# Dosing_CTRLR_HMI.net
KiCad netlist of a schematic drawn in EAGLE
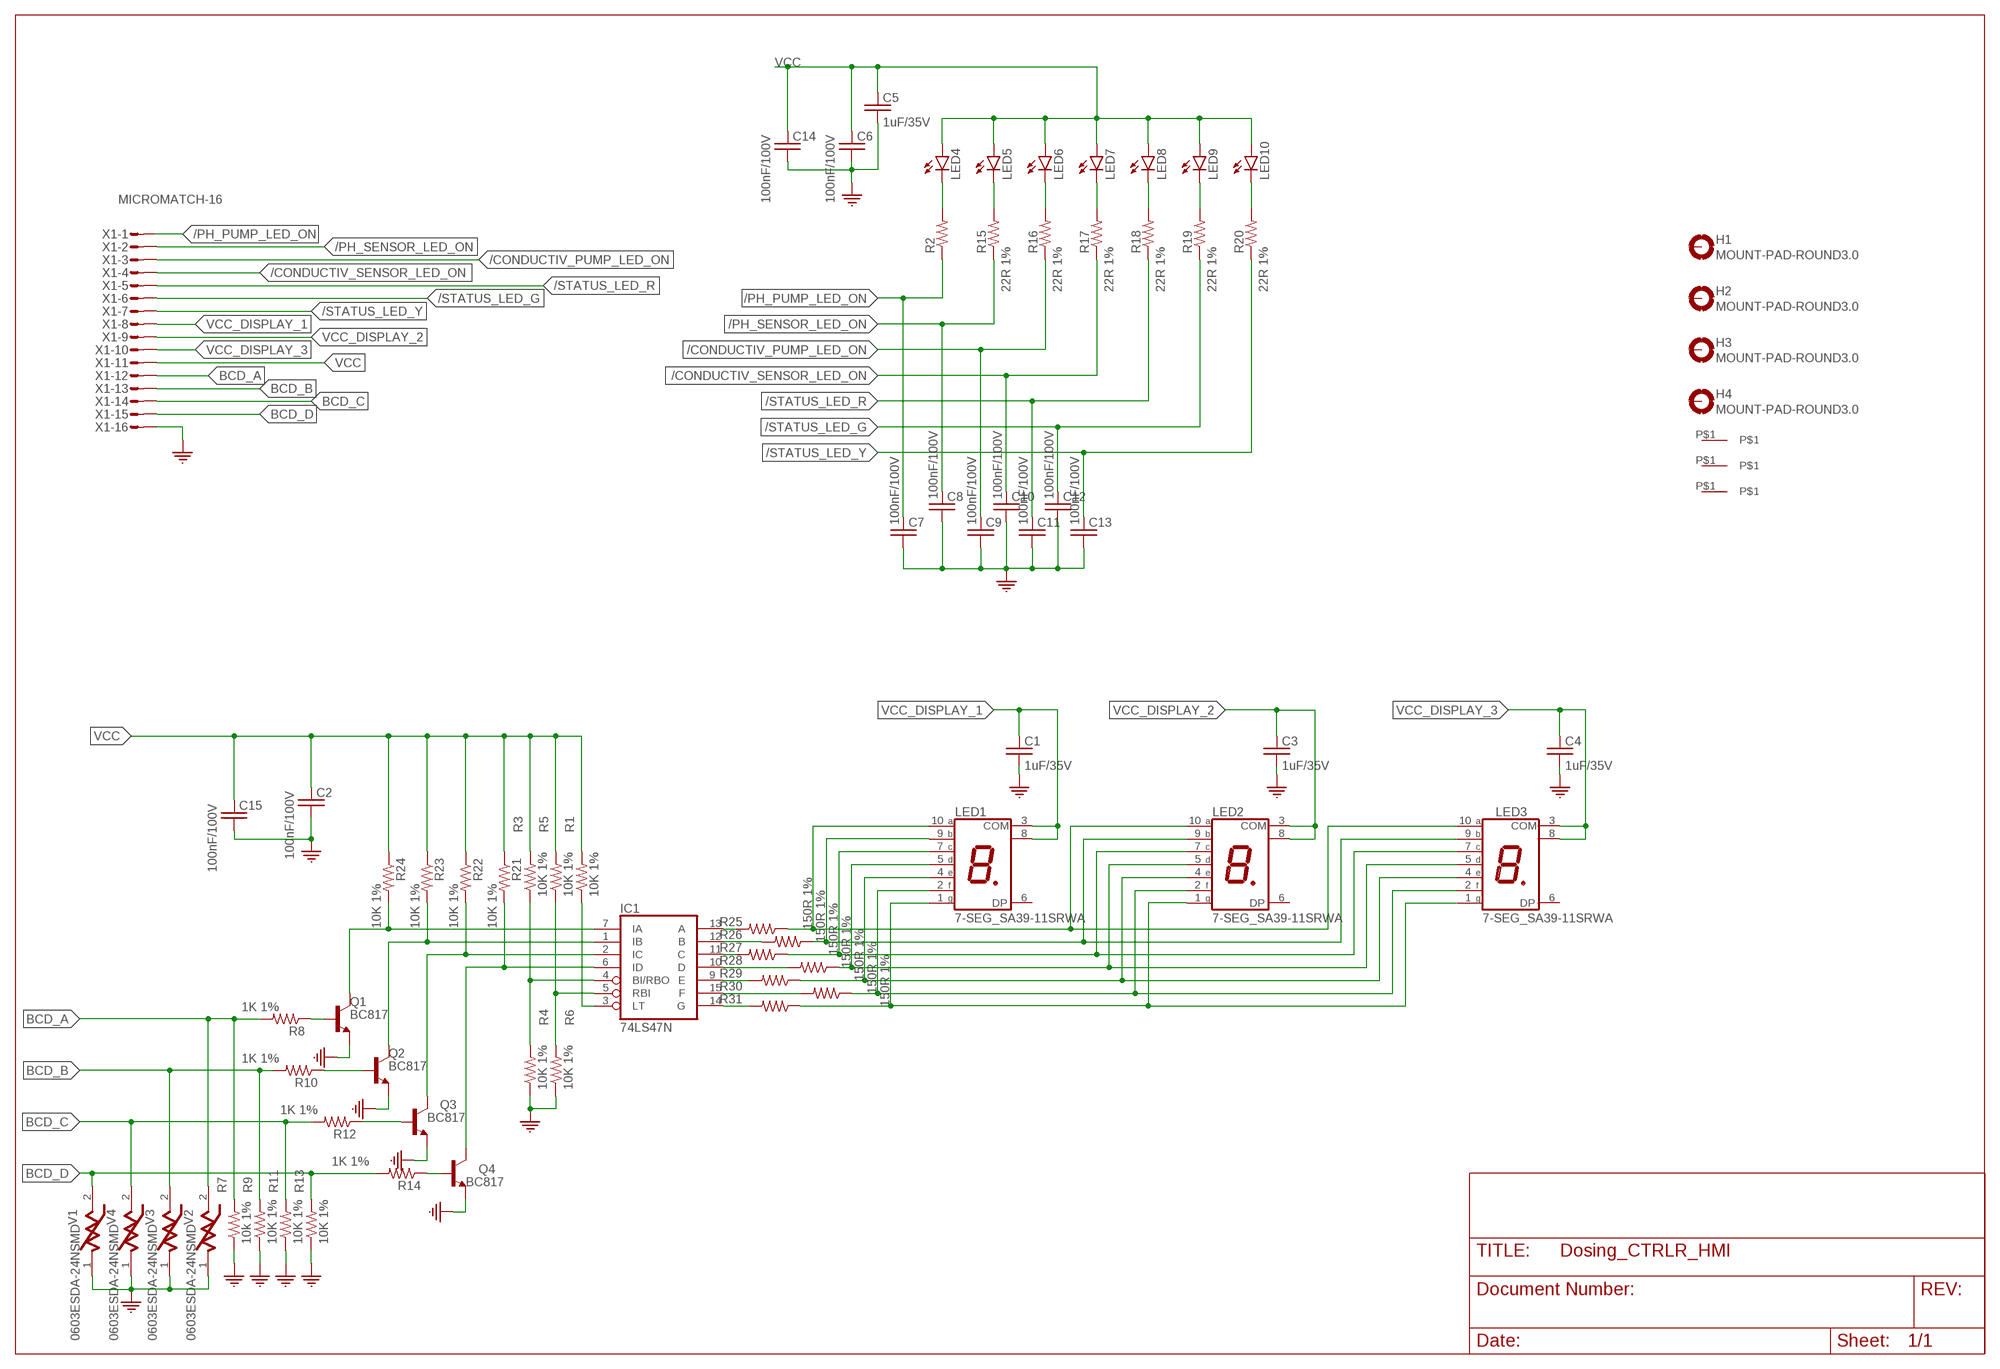
[diagram p0: schematic, sheet 1]

(export (version "E")
  (design (tool "Eeschema 10.0.6"))
  (components
    (comp (ref "C1")
      (value "1uF/35V")
      (footprint "eagle-import:EIA0603")
      (libsource (lib "eagle-import") (part "C_0603EIA0603"))
    )
    (comp (ref "C2")
      (value "100nF/100V")
      (footprint "eagle-import:EIA0603")
      (libsource (lib "eagle-import") (part "C_0603EIA0603"))
    )
    (comp (ref "C3")
      (value "1uF/35V")
      (footprint "eagle-import:EIA0603")
      (libsource (lib "eagle-import") (part "C_0603EIA0603"))
    )
    (comp (ref "C4")
      (value "1uF/35V")
      (footprint "eagle-import:EIA0603")
      (libsource (lib "eagle-import") (part "C_0603EIA0603"))
    )
    (comp (ref "C5")
      (value "1uF/35V")
      (footprint "eagle-import:EIA0603")
      (libsource (lib "eagle-import") (part "C_0603EIA0603"))
    )
    (comp (ref "C6")
      (value "100nF/100V")
      (footprint "eagle-import:EIA0603")
      (libsource (lib "eagle-import") (part "C_0603EIA0603"))
    )
    (comp (ref "C7")
      (value "100nF/100V")
      (footprint "eagle-import:EIA0603")
      (libsource (lib "eagle-import") (part "C_0603EIA0603"))
    )
    (comp (ref "C8")
      (value "100nF/100V")
      (footprint "eagle-import:EIA0603")
      (libsource (lib "eagle-import") (part "C_0603EIA0603"))
    )
    (comp (ref "C9")
      (value "100nF/100V")
      (footprint "eagle-import:EIA0603")
      (libsource (lib "eagle-import") (part "C_0603EIA0603"))
    )
    (comp (ref "C10")
      (value "100nF/100V")
      (footprint "eagle-import:EIA0603")
      (libsource (lib "eagle-import") (part "C_0603EIA0603"))
    )
    (comp (ref "C11")
      (value "100nF/100V")
      (footprint "eagle-import:EIA0603")
      (libsource (lib "eagle-import") (part "C_0603EIA0603"))
    )
    (comp (ref "C12")
      (value "100nF/100V")
      (footprint "eagle-import:EIA0603")
      (libsource (lib "eagle-import") (part "C_0603EIA0603"))
    )
    (comp (ref "C13")
      (value "100nF/100V")
      (footprint "eagle-import:EIA0603")
      (libsource (lib "eagle-import") (part "C_0603EIA0603"))
    )
    (comp (ref "C14")
      (value "100nF/100V")
      (footprint "eagle-import:EIA0603")
      (libsource (lib "eagle-import") (part "C_0603EIA0603"))
    )
    (comp (ref "C15")
      (value "100nF/100V")
      (footprint "eagle-import:EIA0603")
      (libsource (lib "eagle-import") (part "C_0603EIA0603"))
    )
    (comp (ref "FID1")
      (value "FIDUCIAL")
      (footprint "eagle-import:FIDUCIAL")
      (libsource (lib "eagle-import") (part "FIDUCIAL"))
    )
    (comp (ref "FID2")
      (value "FIDUCIAL")
      (footprint "eagle-import:FIDUCIAL")
      (libsource (lib "eagle-import") (part "FIDUCIAL"))
    )
    (comp (ref "FID3")
      (value "FIDUCIAL")
      (footprint "eagle-import:FIDUCIAL")
      (libsource (lib "eagle-import") (part "FIDUCIAL"))
    )
    (comp (ref "H1")
      (value "MOUNT-PAD-ROUND3.0")
      (footprint "eagle-import:3,0-PAD")
      (libsource (lib "eagle-import") (part "MOUNT-PAD-ROUND3.0"))
    )
    (comp (ref "H2")
      (value "MOUNT-PAD-ROUND3.0")
      (footprint "eagle-import:3,0-PAD")
      (libsource (lib "eagle-import") (part "MOUNT-PAD-ROUND3.0"))
    )
    (comp (ref "H3")
      (value "MOUNT-PAD-ROUND3.0")
      (footprint "eagle-import:3,0-PAD")
      (libsource (lib "eagle-import") (part "MOUNT-PAD-ROUND3.0"))
    )
    (comp (ref "H4")
      (value "MOUNT-PAD-ROUND3.0")
      (footprint "eagle-import:3,0-PAD")
      (libsource (lib "eagle-import") (part "MOUNT-PAD-ROUND3.0"))
    )
    (comp (ref "IC1")
      (value "74LS47N")
      (footprint "eagle-import:DIL16")
      (libsource (lib "eagle-import") (part "7447NLS"))
    )
    (comp (ref "LED1")
      (value "7-SEG_SA39-11SRWA")
      (footprint "eagle-import:SA39-11SRWA")
      (libsource (lib "eagle-import") (part "7-SEG_SA39-11SRWA"))
    )
    (comp (ref "LED2")
      (value "7-SEG_SA39-11SRWA")
      (footprint "eagle-import:SA39-11SRWA")
      (libsource (lib "eagle-import") (part "7-SEG_SA39-11SRWA"))
    )
    (comp (ref "LED3")
      (value "7-SEG_SA39-11SRWA")
      (footprint "eagle-import:SA39-11SRWA")
      (libsource (lib "eagle-import") (part "7-SEG_SA39-11SRWA"))
    )
    (comp (ref "LED4")
      (value "LED5MM")
      (footprint "eagle-import:LED5MM")
      (libsource (lib "eagle-import") (part "LED5MM"))
    )
    (comp (ref "LED5")
      (value "LED5MM")
      (footprint "eagle-import:LED5MM")
      (libsource (lib "eagle-import") (part "LED5MM"))
    )
    (comp (ref "LED6")
      (value "LED5MM")
      (footprint "eagle-import:LED5MM")
      (libsource (lib "eagle-import") (part "LED5MM"))
    )
    (comp (ref "LED7")
      (value "LED5MM")
      (footprint "eagle-import:LED5MM")
      (libsource (lib "eagle-import") (part "LED5MM"))
    )
    (comp (ref "LED8")
      (value "LED5MM")
      (footprint "eagle-import:LED5MM")
      (libsource (lib "eagle-import") (part "LED5MM"))
    )
    (comp (ref "LED9")
      (value "LED5MM")
      (footprint "eagle-import:LED5MM")
      (libsource (lib "eagle-import") (part "LED5MM"))
    )
    (comp (ref "LED10")
      (value "LED5MM")
      (footprint "eagle-import:LED5MM")
      (libsource (lib "eagle-import") (part "LED5MM"))
    )
    (comp (ref "Q1")
      (value "BC817")
      (footprint "eagle-import:SOT23")
      (fields (field (name "MFR") "NXP"))
      (libsource (lib "eagle-import") (part "BC817"))
    )
    (comp (ref "Q2")
      (value "BC817")
      (footprint "eagle-import:SOT23")
      (fields (field (name "MFR") "NXP"))
      (libsource (lib "eagle-import") (part "BC817"))
    )
    (comp (ref "Q3")
      (value "BC817")
      (footprint "eagle-import:SOT23")
      (fields (field (name "MFR") "NXP"))
      (libsource (lib "eagle-import") (part "BC817"))
    )
    (comp (ref "Q4")
      (value "BC817")
      (footprint "eagle-import:SOT23")
      (fields (field (name "MFR") "NXP"))
      (libsource (lib "eagle-import") (part "BC817"))
    )
    (comp (ref "R1")
      (value "10K 1%")
      (footprint "eagle-import:EIA0603")
      (libsource (lib "eagle-import") (part "R_0603"))
    )
    (comp (ref "R2")
      (value "22R 1%")
      (footprint "eagle-import:EIA1206")
      (libsource (lib "eagle-import") (part "R_1206EIA1206"))
    )
    (comp (ref "R3")
      (value "10K 1%")
      (footprint "eagle-import:EIA0603")
      (libsource (lib "eagle-import") (part "R_0603"))
    )
    (comp (ref "R4")
      (value "10K 1%")
      (footprint "eagle-import:EIA0603")
      (libsource (lib "eagle-import") (part "R_0603"))
    )
    (comp (ref "R5")
      (value "10K 1%")
      (footprint "eagle-import:EIA0603")
      (libsource (lib "eagle-import") (part "R_0603"))
    )
    (comp (ref "R6")
      (value "10K 1%")
      (footprint "eagle-import:EIA0603")
      (libsource (lib "eagle-import") (part "R_0603"))
    )
    (comp (ref "R7")
      (value "10k 1%")
      (footprint "eagle-import:EIA0603")
      (libsource (lib "eagle-import") (part "R_0603"))
    )
    (comp (ref "R8")
      (value "1K 1%")
      (footprint "eagle-import:EIA0603")
      (libsource (lib "eagle-import") (part "R_0603"))
    )
    (comp (ref "R9")
      (value "10K 1%")
      (footprint "eagle-import:EIA0603")
      (libsource (lib "eagle-import") (part "R_0603"))
    )
    (comp (ref "R10")
      (value "1K 1%")
      (footprint "eagle-import:EIA0603")
      (libsource (lib "eagle-import") (part "R_0603"))
    )
    (comp (ref "R11")
      (value "10K 1%")
      (footprint "eagle-import:EIA0603")
      (libsource (lib "eagle-import") (part "R_0603"))
    )
    (comp (ref "R12")
      (value "1K 1%")
      (footprint "eagle-import:EIA0603")
      (libsource (lib "eagle-import") (part "R_0603"))
    )
    (comp (ref "R13")
      (value "10K 1%")
      (footprint "eagle-import:EIA0603")
      (libsource (lib "eagle-import") (part "R_0603"))
    )
    (comp (ref "R14")
      (value "1K 1%")
      (footprint "eagle-import:EIA0603")
      (libsource (lib "eagle-import") (part "R_0603"))
    )
    (comp (ref "R15")
      (value "22R 1%")
      (footprint "eagle-import:EIA1206")
      (libsource (lib "eagle-import") (part "R_1206EIA1206"))
    )
    (comp (ref "R16")
      (value "22R 1%")
      (footprint "eagle-import:EIA1206")
      (libsource (lib "eagle-import") (part "R_1206EIA1206"))
    )
    (comp (ref "R17")
      (value "22R 1%")
      (footprint "eagle-import:EIA1206")
      (libsource (lib "eagle-import") (part "R_1206EIA1206"))
    )
    (comp (ref "R18")
      (value "22R 1%")
      (footprint "eagle-import:EIA1206")
      (libsource (lib "eagle-import") (part "R_1206EIA1206"))
    )
    (comp (ref "R19")
      (value "22R 1%")
      (footprint "eagle-import:EIA1206")
      (libsource (lib "eagle-import") (part "R_1206EIA1206"))
    )
    (comp (ref "R20")
      (value "22R 1%")
      (footprint "eagle-import:EIA1206")
      (libsource (lib "eagle-import") (part "R_1206EIA1206"))
    )
    (comp (ref "R21")
      (value "10K 1%")
      (footprint "eagle-import:EIA0603")
      (libsource (lib "eagle-import") (part "R_0603"))
    )
    (comp (ref "R22")
      (value "10K 1%")
      (footprint "eagle-import:EIA0603")
      (libsource (lib "eagle-import") (part "R_0603"))
    )
    (comp (ref "R23")
      (value "10K 1%")
      (footprint "eagle-import:EIA0603")
      (libsource (lib "eagle-import") (part "R_0603"))
    )
    (comp (ref "R24")
      (value "10K 1%")
      (footprint "eagle-import:EIA0603")
      (libsource (lib "eagle-import") (part "R_0603"))
    )
    (comp (ref "R25")
      (value "150R 1%")
      (footprint "eagle-import:EIA1206")
      (libsource (lib "eagle-import") (part "R_1206EIA1206"))
    )
    (comp (ref "R26")
      (value "150R 1%")
      (footprint "eagle-import:EIA1206")
      (libsource (lib "eagle-import") (part "R_1206EIA1206"))
    )
    (comp (ref "R27")
      (value "150R 1%")
      (footprint "eagle-import:EIA1206")
      (libsource (lib "eagle-import") (part "R_1206EIA1206"))
    )
    (comp (ref "R28")
      (value "150R 1%")
      (footprint "eagle-import:EIA1206")
      (libsource (lib "eagle-import") (part "R_1206EIA1206"))
    )
    (comp (ref "R29")
      (value "150R 1%")
      (footprint "eagle-import:EIA1206")
      (libsource (lib "eagle-import") (part "R_1206EIA1206"))
    )
    (comp (ref "R30")
      (value "150R 1%")
      (footprint "eagle-import:EIA1206")
      (libsource (lib "eagle-import") (part "R_1206EIA1206"))
    )
    (comp (ref "R31")
      (value "150R 1%")
      (footprint "eagle-import:EIA1206")
      (libsource (lib "eagle-import") (part "R_1206EIA1206"))
    )
    (comp (ref "V1")
      (value "0603ESDA-24NSMD")
      (footprint "eagle-import:EIA0603")
      (fields (field (name "MFR") "Bourns"))
      (libsource (lib "eagle-import") (part "0603ESDA-24NSMD"))
    )
    (comp (ref "V2")
      (value "0603ESDA-24NSMD")
      (footprint "eagle-import:EIA0603")
      (fields (field (name "MFR") "Bourns"))
      (libsource (lib "eagle-import") (part "0603ESDA-24NSMD"))
    )
    (comp (ref "V3")
      (value "0603ESDA-24NSMD")
      (footprint "eagle-import:EIA0603")
      (fields (field (name "MFR") "Bourns"))
      (libsource (lib "eagle-import") (part "0603ESDA-24NSMD"))
    )
    (comp (ref "V4")
      (value "0603ESDA-24NSMD")
      (footprint "eagle-import:EIA0603")
      (fields (field (name "MFR") "Bourns"))
      (libsource (lib "eagle-import") (part "0603ESDA-24NSMD"))
    )
    (comp (ref "X1")
      (value "MICROMATCH-16")
      (footprint "eagle-import:MICROMATCH-16")
      (fields (field (name "MF") "FARNELL") (field (name "MPN") "8-215464-6"))
      (libsource (lib "eagle-import") (part "MICROMATCH-16"))
    )
  )
  (nets
    (net (code "1") (name "BCD_A") (class "Default")
      (node (ref "R7") (pin "2") (pinfunction "2_2") (pintype "passive"))
      (node (ref "R8") (pin "2") (pinfunction "2_2") (pintype "passive"))
      (node (ref "V2") (pin "2") (pinfunction "2_2") (pintype "passive"))
      (node (ref "X1") (pin "12") (pinfunction "S_12") (pintype "passive"))
    )
    (net (code "2") (name "BCD_B") (class "Default")
      (node (ref "R10") (pin "2") (pinfunction "2_2") (pintype "passive"))
      (node (ref "R9") (pin "2") (pinfunction "2_2") (pintype "passive"))
      (node (ref "V3") (pin "2") (pinfunction "2_2") (pintype "passive"))
      (node (ref "X1") (pin "13") (pinfunction "S_13") (pintype "passive"))
    )
    (net (code "3") (name "BCD_C") (class "Default")
      (node (ref "R11") (pin "2") (pinfunction "2_2") (pintype "passive"))
      (node (ref "R12") (pin "2") (pinfunction "2_2") (pintype "passive"))
      (node (ref "V4") (pin "2") (pinfunction "2_2") (pintype "passive"))
      (node (ref "X1") (pin "14") (pinfunction "S_14") (pintype "passive"))
    )
    (net (code "4") (name "BCD_D") (class "Default")
      (node (ref "R13") (pin "2") (pinfunction "2_2") (pintype "passive"))
      (node (ref "R14") (pin "2") (pinfunction "2_2") (pintype "passive"))
      (node (ref "V1") (pin "2") (pinfunction "2_2") (pintype "passive"))
      (node (ref "X1") (pin "15") (pinfunction "S_15") (pintype "passive"))
    )
    (net (code "5") (name "GND") (class "Default")
      (node (ref "C1") (pin "2") (pinfunction "2_2") (pintype "passive"))
      (node (ref "C10") (pin "2") (pinfunction "2_2") (pintype "passive"))
      (node (ref "C11") (pin "2") (pinfunction "2_2") (pintype "passive"))
      (node (ref "C12") (pin "2") (pinfunction "2_2") (pintype "passive"))
      (node (ref "C13") (pin "2") (pinfunction "2_2") (pintype "passive"))
      (node (ref "C14") (pin "2") (pinfunction "2_2") (pintype "passive"))
      (node (ref "C15") (pin "2") (pinfunction "2_2") (pintype "passive"))
      (node (ref "C2") (pin "2") (pinfunction "2_2") (pintype "passive"))
      (node (ref "C3") (pin "2") (pinfunction "2_2") (pintype "passive"))
      (node (ref "C4") (pin "2") (pinfunction "2_2") (pintype "passive"))
      (node (ref "C5") (pin "2") (pinfunction "2_2") (pintype "passive"))
      (node (ref "C6") (pin "2") (pinfunction "2_2") (pintype "passive"))
      (node (ref "C7") (pin "2") (pinfunction "2_2") (pintype "passive"))
      (node (ref "C8") (pin "2") (pinfunction "2_2") (pintype "passive"))
      (node (ref "C9") (pin "2") (pinfunction "2_2") (pintype "passive"))
      (node (ref "Q1") (pin "2") (pinfunction "E_2") (pintype "passive"))
      (node (ref "Q2") (pin "2") (pinfunction "E_2") (pintype "passive"))
      (node (ref "Q3") (pin "2") (pinfunction "E_2") (pintype "passive"))
      (node (ref "Q4") (pin "2") (pinfunction "E_2") (pintype "passive"))
      (node (ref "R11") (pin "1") (pinfunction "1_1") (pintype "passive"))
      (node (ref "R13") (pin "1") (pinfunction "1_1") (pintype "passive"))
      (node (ref "R4") (pin "1") (pinfunction "1_1") (pintype "passive"))
      (node (ref "R6") (pin "1") (pinfunction "1_1") (pintype "passive"))
      (node (ref "R7") (pin "1") (pinfunction "1_1") (pintype "passive"))
      (node (ref "R9") (pin "1") (pinfunction "1_1") (pintype "passive"))
      (node (ref "V1") (pin "1") (pinfunction "1_1") (pintype "passive"))
      (node (ref "V2") (pin "1") (pinfunction "1_1") (pintype "passive"))
      (node (ref "V3") (pin "1") (pinfunction "1_1") (pintype "passive"))
      (node (ref "V4") (pin "1") (pinfunction "1_1") (pintype "passive"))
      (node (ref "X1") (pin "16") (pinfunction "S_16") (pintype "passive"))
    )
    (net (code "6") (name "Net-(IC1A-A)") (class "Default")
      (node (ref "IC1") (pin "13") (pinfunction "A_13") (pintype "output"))
      (node (ref "R25") (pin "2") (pinfunction "2_2") (pintype "passive"))
    )
    (net (code "7") (name "Net-(IC1A-B)") (class "Default")
      (node (ref "IC1") (pin "12") (pinfunction "B_12") (pintype "output"))
      (node (ref "R26") (pin "2") (pinfunction "2_2") (pintype "passive"))
    )
    (net (code "8") (name "Net-(IC1A-BI{slash}RBO)") (class "Default")
      (node (ref "IC1") (pin "4") (pinfunction "BI/RBO_4") (pintype "input"))
      (node (ref "R3") (pin "1") (pinfunction "1_1") (pintype "passive"))
      (node (ref "R4") (pin "2") (pinfunction "2_2") (pintype "passive"))
    )
    (net (code "9") (name "Net-(IC1A-C)") (class "Default")
      (node (ref "IC1") (pin "11") (pinfunction "C_11") (pintype "output"))
      (node (ref "R27") (pin "2") (pinfunction "2_2") (pintype "passive"))
    )
    (net (code "10") (name "Net-(IC1A-D)") (class "Default")
      (node (ref "IC1") (pin "10") (pinfunction "D_10") (pintype "output"))
      (node (ref "R28") (pin "2") (pinfunction "2_2") (pintype "passive"))
    )
    (net (code "11") (name "Net-(IC1A-E)") (class "Default")
      (node (ref "IC1") (pin "9") (pinfunction "E_9") (pintype "output"))
      (node (ref "R29") (pin "2") (pinfunction "2_2") (pintype "passive"))
    )
    (net (code "12") (name "Net-(IC1A-F)") (class "Default")
      (node (ref "IC1") (pin "15") (pinfunction "F_15") (pintype "output"))
      (node (ref "R30") (pin "2") (pinfunction "2_2") (pintype "passive"))
    )
    (net (code "13") (name "Net-(IC1A-G)") (class "Default")
      (node (ref "IC1") (pin "14") (pinfunction "G_14") (pintype "output"))
      (node (ref "R31") (pin "2") (pinfunction "2_2") (pintype "passive"))
    )
    (net (code "14") (name "Net-(IC1A-IA)") (class "Default")
      (node (ref "IC1") (pin "7") (pinfunction "IA_7") (pintype "input"))
      (node (ref "Q1") (pin "3") (pinfunction "C_3") (pintype "passive"))
      (node (ref "R24") (pin "2") (pinfunction "2_2") (pintype "passive"))
    )
    (net (code "15") (name "Net-(IC1A-IB)") (class "Default")
      (node (ref "IC1") (pin "1") (pinfunction "IB_1") (pintype "input"))
      (node (ref "Q2") (pin "3") (pinfunction "C_3") (pintype "passive"))
      (node (ref "R23") (pin "2") (pinfunction "2_2") (pintype "passive"))
    )
    (net (code "16") (name "Net-(IC1A-IC)") (class "Default")
      (node (ref "IC1") (pin "2") (pinfunction "IC_2") (pintype "input"))
      (node (ref "Q3") (pin "3") (pinfunction "C_3") (pintype "passive"))
      (node (ref "R22") (pin "2") (pinfunction "2_2") (pintype "passive"))
    )
    (net (code "17") (name "Net-(IC1A-ID)") (class "Default")
      (node (ref "IC1") (pin "6") (pinfunction "ID_6") (pintype "input"))
      (node (ref "Q4") (pin "3") (pinfunction "C_3") (pintype "passive"))
      (node (ref "R21") (pin "2") (pinfunction "2_2") (pintype "passive"))
    )
    (net (code "18") (name "Net-(IC1A-LT)") (class "Default")
      (node (ref "IC1") (pin "3") (pinfunction "LT_3") (pintype "input"))
      (node (ref "R1") (pin "1") (pinfunction "1_1") (pintype "passive"))
    )
    (net (code "19") (name "Net-(IC1A-RBI)") (class "Default")
      (node (ref "IC1") (pin "5") (pinfunction "RBI_5") (pintype "input"))
      (node (ref "R5") (pin "1") (pinfunction "1_1") (pintype "passive"))
      (node (ref "R6") (pin "2") (pinfunction "2_2") (pintype "passive"))
    )
    (net (code "20") (name "Net-(LED1-A)") (class "Default")
      (node (ref "LED1") (pin "10") (pinfunction "A_10") (pintype "passive"))
      (node (ref "LED2") (pin "10") (pinfunction "A_10") (pintype "passive"))
      (node (ref "LED3") (pin "10") (pinfunction "A_10") (pintype "passive"))
      (node (ref "R25") (pin "1") (pinfunction "1_1") (pintype "passive"))
    )
    (net (code "21") (name "Net-(LED1-B)") (class "Default")
      (node (ref "LED1") (pin "9") (pinfunction "B_9") (pintype "passive"))
      (node (ref "LED2") (pin "9") (pinfunction "B_9") (pintype "passive"))
      (node (ref "LED3") (pin "9") (pinfunction "B_9") (pintype "passive"))
      (node (ref "R26") (pin "1") (pinfunction "1_1") (pintype "passive"))
    )
    (net (code "22") (name "Net-(LED1-C)") (class "Default")
      (node (ref "LED1") (pin "7") (pinfunction "C_7") (pintype "passive"))
      (node (ref "LED2") (pin "7") (pinfunction "C_7") (pintype "passive"))
      (node (ref "LED3") (pin "7") (pinfunction "C_7") (pintype "passive"))
      (node (ref "R27") (pin "1") (pinfunction "1_1") (pintype "passive"))
    )
    (net (code "23") (name "Net-(LED1-D)") (class "Default")
      (node (ref "LED1") (pin "5") (pinfunction "D_5") (pintype "passive"))
      (node (ref "LED2") (pin "5") (pinfunction "D_5") (pintype "passive"))
      (node (ref "LED3") (pin "5") (pinfunction "D_5") (pintype "passive"))
      (node (ref "R28") (pin "1") (pinfunction "1_1") (pintype "passive"))
    )
    (net (code "24") (name "Net-(LED1-E)") (class "Default")
      (node (ref "LED1") (pin "4") (pinfunction "E_4") (pintype "passive"))
      (node (ref "LED2") (pin "4") (pinfunction "E_4") (pintype "passive"))
      (node (ref "LED3") (pin "4") (pinfunction "E_4") (pintype "passive"))
      (node (ref "R29") (pin "1") (pinfunction "1_1") (pintype "passive"))
    )
    (net (code "25") (name "Net-(LED1-F)") (class "Default")
      (node (ref "LED1") (pin "2") (pinfunction "F_2") (pintype "passive"))
      (node (ref "LED2") (pin "2") (pinfunction "F_2") (pintype "passive"))
      (node (ref "LED3") (pin "2") (pinfunction "F_2") (pintype "passive"))
      (node (ref "R30") (pin "1") (pinfunction "1_1") (pintype "passive"))
    )
    (net (code "26") (name "Net-(LED1-G)") (class "Default")
      (node (ref "LED1") (pin "1") (pinfunction "G_1") (pintype "passive"))
      (node (ref "LED2") (pin "1") (pinfunction "G_1") (pintype "passive"))
      (node (ref "LED3") (pin "1") (pinfunction "G_1") (pintype "passive"))
      (node (ref "R31") (pin "1") (pinfunction "1_1") (pintype "passive"))
    )
    (net (code "27") (name "Net-(LED4-C)") (class "Default")
      (node (ref "LED4") (pin "K") (pinfunction "C_K") (pintype "passive"))
      (node (ref "R2") (pin "2") (pinfunction "2_2") (pintype "passive"))
    )
    (net (code "28") (name "Net-(LED5-C)") (class "Default")
      (node (ref "LED5") (pin "K") (pinfunction "C_K") (pintype "passive"))
      (node (ref "R15") (pin "2") (pinfunction "2_2") (pintype "passive"))
    )
    (net (code "29") (name "Net-(LED6-C)") (class "Default")
      (node (ref "LED6") (pin "K") (pinfunction "C_K") (pintype "passive"))
      (node (ref "R16") (pin "2") (pinfunction "2_2") (pintype "passive"))
    )
    (net (code "30") (name "Net-(LED7-C)") (class "Default")
      (node (ref "LED7") (pin "K") (pinfunction "C_K") (pintype "passive"))
      (node (ref "R17") (pin "2") (pinfunction "2_2") (pintype "passive"))
    )
    (net (code "31") (name "Net-(LED8-C)") (class "Default")
      (node (ref "LED8") (pin "K") (pinfunction "C_K") (pintype "passive"))
      (node (ref "R18") (pin "2") (pinfunction "2_2") (pintype "passive"))
    )
    (net (code "32") (name "Net-(LED9-C)") (class "Default")
      (node (ref "LED9") (pin "K") (pinfunction "C_K") (pintype "passive"))
      (node (ref "R19") (pin "2") (pinfunction "2_2") (pintype "passive"))
    )
    (net (code "33") (name "Net-(LED10-C)") (class "Default")
      (node (ref "LED10") (pin "K") (pinfunction "C_K") (pintype "passive"))
      (node (ref "R20") (pin "2") (pinfunction "2_2") (pintype "passive"))
    )
    (net (code "34") (name "Net-(Q1-B)") (class "Default")
      (node (ref "Q1") (pin "1") (pinfunction "B_1") (pintype "passive"))
      (node (ref "R8") (pin "1") (pinfunction "1_1") (pintype "passive"))
    )
    (net (code "35") (name "Net-(Q2-B)") (class "Default")
      (node (ref "Q2") (pin "1") (pinfunction "B_1") (pintype "passive"))
      (node (ref "R10") (pin "1") (pinfunction "1_1") (pintype "passive"))
    )
    (net (code "36") (name "Net-(Q3-B)") (class "Default")
      (node (ref "Q3") (pin "1") (pinfunction "B_1") (pintype "passive"))
      (node (ref "R12") (pin "1") (pinfunction "1_1") (pintype "passive"))
    )
    (net (code "37") (name "Net-(Q4-B)") (class "Default")
      (node (ref "Q4") (pin "1") (pinfunction "B_1") (pintype "passive"))
      (node (ref "R14") (pin "1") (pinfunction "1_1") (pintype "passive"))
    )
    (net (code "38") (name "VCC") (class "Default")
      (node (ref "C14") (pin "1") (pinfunction "1_1") (pintype "passive"))
      (node (ref "C15") (pin "1") (pinfunction "1_1") (pintype "passive"))
      (node (ref "C2") (pin "1") (pinfunction "1_1") (pintype "passive"))
      (node (ref "C5") (pin "1") (pinfunction "1_1") (pintype "passive"))
      (node (ref "C6") (pin "1") (pinfunction "1_1") (pintype "passive"))
      (node (ref "LED10") (pin "A") (pinfunction "A_A") (pintype "passive"))
      (node (ref "LED4") (pin "A") (pinfunction "A_A") (pintype "passive"))
      (node (ref "LED5") (pin "A") (pinfunction "A_A") (pintype "passive"))
      (node (ref "LED6") (pin "A") (pinfunction "A_A") (pintype "passive"))
      (node (ref "LED7") (pin "A") (pinfunction "A_A") (pintype "passive"))
      (node (ref "LED8") (pin "A") (pinfunction "A_A") (pintype "passive"))
      (node (ref "LED9") (pin "A") (pinfunction "A_A") (pintype "passive"))
      (node (ref "R1") (pin "2") (pinfunction "2_2") (pintype "passive"))
      (node (ref "R21") (pin "1") (pinfunction "1_1") (pintype "passive"))
      (node (ref "R22") (pin "1") (pinfunction "1_1") (pintype "passive"))
      (node (ref "R23") (pin "1") (pinfunction "1_1") (pintype "passive"))
      (node (ref "R24") (pin "1") (pinfunction "1_1") (pintype "passive"))
      (node (ref "R3") (pin "2") (pinfunction "2_2") (pintype "passive"))
      (node (ref "R5") (pin "2") (pinfunction "2_2") (pintype "passive"))
      (node (ref "X1") (pin "11") (pinfunction "S_11") (pintype "passive"))
    )
    (net (code "39") (name "VCC_DISPLAY_1") (class "Default")
      (node (ref "C1") (pin "1") (pinfunction "1_1") (pintype "passive"))
      (node (ref "LED1") (pin "3") (pinfunction "COM_3") (pintype "passive"))
      (node (ref "LED1") (pin "8") (pinfunction "COM_8") (pintype "passive"))
      (node (ref "X1") (pin "8") (pinfunction "S_8") (pintype "passive"))
    )
    (net (code "40") (name "VCC_DISPLAY_2") (class "Default")
      (node (ref "C3") (pin "1") (pinfunction "1_1") (pintype "passive"))
      (node (ref "LED2") (pin "3") (pinfunction "COM_3") (pintype "passive"))
      (node (ref "LED2") (pin "8") (pinfunction "COM_8") (pintype "passive"))
      (node (ref "X1") (pin "9") (pinfunction "S_9") (pintype "passive"))
    )
    (net (code "41") (name "VCC_DISPLAY_3") (class "Default")
      (node (ref "C4") (pin "1") (pinfunction "1_1") (pintype "passive"))
      (node (ref "LED3") (pin "3") (pinfunction "COM_3") (pintype "passive"))
      (node (ref "LED3") (pin "8") (pinfunction "COM_8") (pintype "passive"))
      (node (ref "X1") (pin "10") (pinfunction "S_10") (pintype "passive"))
    )
    (net (code "42") (name "unconnected-(FID1-PadP$1)") (class "Default")
      (node (ref "FID1") (pin "P$1") (pinfunction "P$1_P$1") (pintype "bidirectional"))
    )
    (net (code "43") (name "unconnected-(FID2-PadP$1)") (class "Default")
      (node (ref "FID2") (pin "P$1") (pinfunction "P$1_P$1") (pintype "bidirectional"))
    )
    (net (code "44") (name "unconnected-(FID3-PadP$1)") (class "Default")
      (node (ref "FID3") (pin "P$1") (pinfunction "P$1_P$1") (pintype "bidirectional"))
    )
    (net (code "45") (name "unconnected-(H1-MOUNT-PadB3,0)") (class "Default")
      (node (ref "H1") (pin "B3,0") (pinfunction "MOUNT_B3,0") (pintype "passive"))
    )
    (net (code "46") (name "unconnected-(H2-MOUNT-PadB3,0)") (class "Default")
      (node (ref "H2") (pin "B3,0") (pinfunction "MOUNT_B3,0") (pintype "passive"))
    )
    (net (code "47") (name "unconnected-(H3-MOUNT-PadB3,0)") (class "Default")
      (node (ref "H3") (pin "B3,0") (pinfunction "MOUNT_B3,0") (pintype "passive"))
    )
    (net (code "48") (name "unconnected-(H4-MOUNT-PadB3,0)") (class "Default")
      (node (ref "H4") (pin "B3,0") (pinfunction "MOUNT_B3,0") (pintype "passive"))
    )
    (net (code "49") (name "unconnected-(LED1-DP-Pad6)") (class "Default")
      (node (ref "LED1") (pin "6") (pinfunction "DP_6") (pintype "passive"))
    )
    (net (code "50") (name "unconnected-(LED2-DP-Pad6)") (class "Default")
      (node (ref "LED2") (pin "6") (pinfunction "DP_6") (pintype "passive"))
    )
    (net (code "51") (name "unconnected-(LED3-DP-Pad6)") (class "Default")
      (node (ref "LED3") (pin "6") (pinfunction "DP_6") (pintype "passive"))
    )
    (net (code "52") (name "{slash}CONDUCTIV_PUMP_LED_ON") (class "Default")
      (node (ref "C9") (pin "1") (pinfunction "1_1") (pintype "passive"))
      (node (ref "R16") (pin "1") (pinfunction "1_1") (pintype "passive"))
      (node (ref "X1") (pin "3") (pinfunction "S_3") (pintype "passive"))
    )
    (net (code "53") (name "{slash}CONDUCTIV_SENSOR_LED_ON") (class "Default")
      (node (ref "C10") (pin "1") (pinfunction "1_1") (pintype "passive"))
      (node (ref "R17") (pin "1") (pinfunction "1_1") (pintype "passive"))
      (node (ref "X1") (pin "4") (pinfunction "S_4") (pintype "passive"))
    )
    (net (code "54") (name "{slash}PH_PUMP_LED_ON") (class "Default")
      (node (ref "C7") (pin "1") (pinfunction "1_1") (pintype "passive"))
      (node (ref "R2") (pin "1") (pinfunction "1_1") (pintype "passive"))
      (node (ref "X1") (pin "1") (pinfunction "S_1") (pintype "passive"))
    )
    (net (code "55") (name "{slash}PH_SENSOR_LED_ON") (class "Default")
      (node (ref "C8") (pin "1") (pinfunction "1_1") (pintype "passive"))
      (node (ref "R15") (pin "1") (pinfunction "1_1") (pintype "passive"))
      (node (ref "X1") (pin "2") (pinfunction "S_2") (pintype "passive"))
    )
    (net (code "56") (name "{slash}STATUS_LED_G") (class "Default")
      (node (ref "C12") (pin "1") (pinfunction "1_1") (pintype "passive"))
      (node (ref "R19") (pin "1") (pinfunction "1_1") (pintype "passive"))
      (node (ref "X1") (pin "6") (pinfunction "S_6") (pintype "passive"))
    )
    (net (code "57") (name "{slash}STATUS_LED_R") (class "Default")
      (node (ref "C11") (pin "1") (pinfunction "1_1") (pintype "passive"))
      (node (ref "R18") (pin "1") (pinfunction "1_1") (pintype "passive"))
      (node (ref "X1") (pin "5") (pinfunction "S_5") (pintype "passive"))
    )
    (net (code "58") (name "{slash}STATUS_LED_Y") (class "Default")
      (node (ref "C13") (pin "1") (pinfunction "1_1") (pintype "passive"))
      (node (ref "R20") (pin "1") (pinfunction "1_1") (pintype "passive"))
      (node (ref "X1") (pin "7") (pinfunction "S_7") (pintype "passive"))
    )
  )
)
